# TachSpeedo.net
KiCad netlist of a schematic drawn in EAGLE
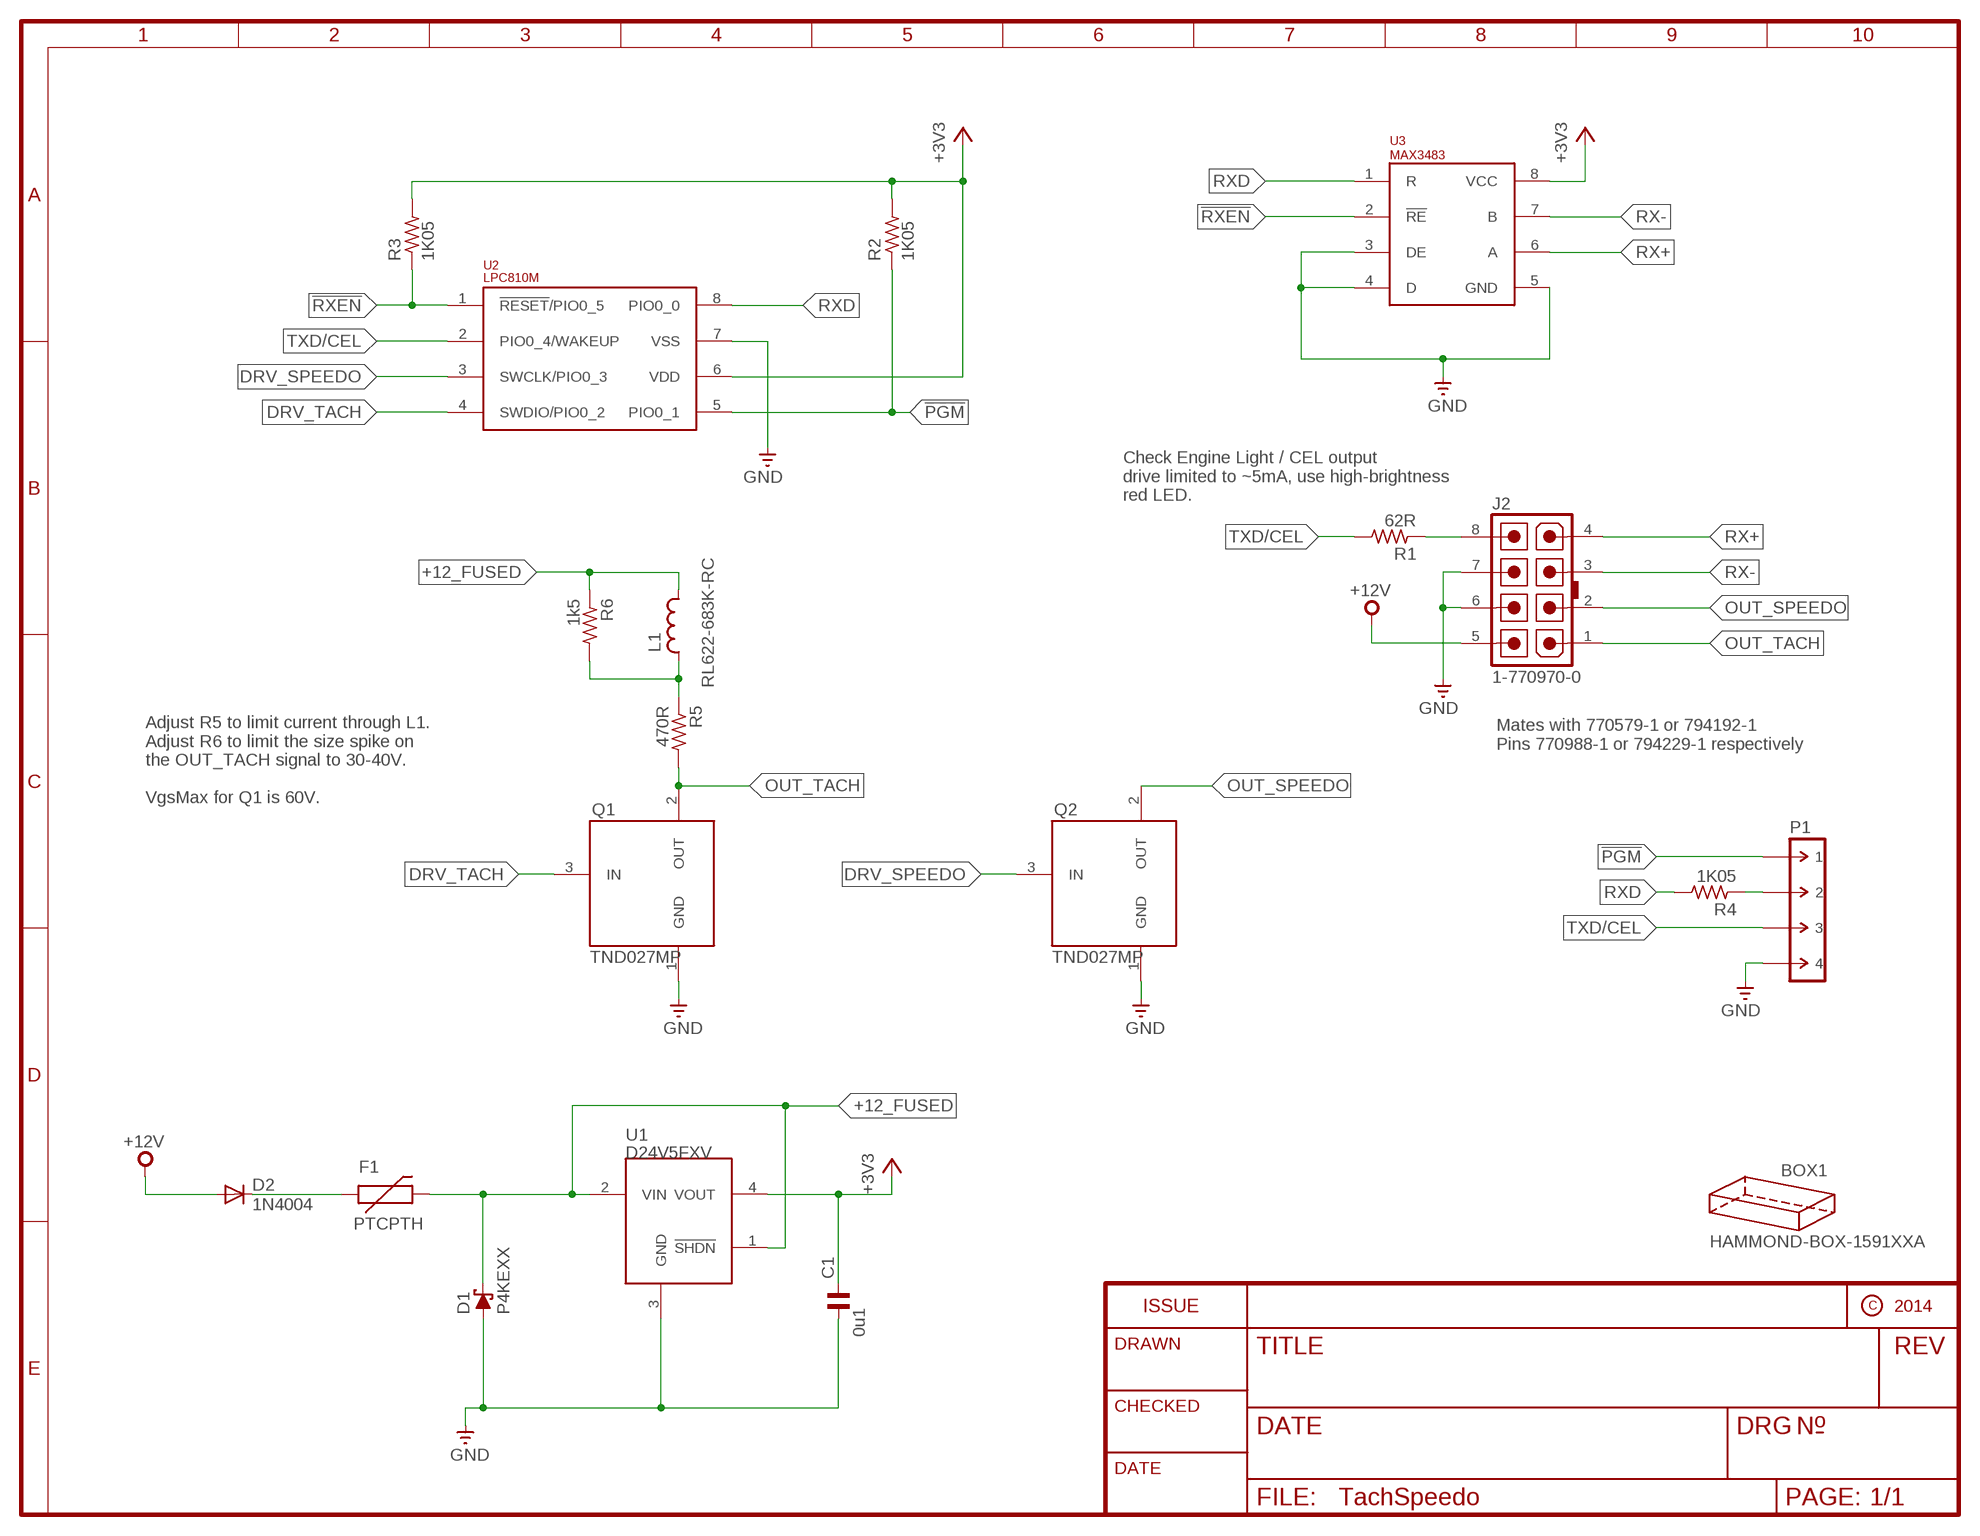
[diagram p0: schematic, sheet 1]

(export (version "E")
  (design (tool "Eeschema 10.0.6"))
  (components
    (comp (ref "BOX1")
      (value "HAMMOND-BOX-1591XXA")
      (footprint "eagle-import:1591XXA")
      (fields (field (name "PARTNO") "1591XXAFLBK"))
      (libsource (lib "eagle-import") (part "HAMMOND-BOX-1591XXA"))
    )
    (comp (ref "C1")
      (value "0u1")
      (footprint "eagle-import:C025-024X044")
      (fields (field (name "PARTNO") "FK18X7R1E104K"))
      (libsource (lib "eagle-import") (part "C-EU025-024X044"))
    )
    (comp (ref "D1")
      (value "P4KEXX")
      (footprint "eagle-import:DO41-10")
      (fields (field (name "PARTNO") "P4KE30CA"))
      (libsource (lib "eagle-import") (part "P4KEXX"))
    )
    (comp (ref "D2")
      (value "1N4004")
      (footprint "eagle-import:DO41-10")
      (libsource (lib "eagle-import") (part "1N4004"))
    )
    (comp (ref "F1")
      (value "PTCPTH")
      (footprint "eagle-import:PTC")
      (fields (field (name "PARTNO") "600R150-RBZR"))
      (libsource (lib "eagle-import") (part "PTCPTH"))
    )
    (comp (ref "J2")
      (value "1-770970-0")
      (footprint "eagle-import:1-770970-0")
      (libsource (lib "eagle-import") (part "1-770970-0"))
    )
    (comp (ref "L1")
      (value "RL622-683K-RC")
      (footprint "eagle-import:RL622")
      (fields (field (name "PARTNO") "RL622-563K-RC"))
      (libsource (lib "eagle-import") (part "RL622"))
    )
    (comp (ref "P1")
      (value "M-1X04-SIP-100-40")
      (footprint "eagle-import:SIP-100-04-40")
      (fields (field (name "PARTNO") "961104-6404-AR"))
      (libsource (lib "eagle-import") (part "M-1X04-SIP-100-40"))
    )
    (comp (ref "Q1")
      (value "TND027MP")
      (footprint "eagle-import:TO-92")
      (fields (field (name "PARTNO") "TND027MP-AZ"))
      (libsource (lib "eagle-import") (part "TND027MP"))
    )
    (comp (ref "Q2")
      (value "TND027MP")
      (footprint "eagle-import:TO-92")
      (fields (field (name "PARTNO") "TND027MP-AZ"))
      (libsource (lib "eagle-import") (part "TND027MP"))
    )
    (comp (ref "R1")
      (value "62R")
      (footprint "eagle-import:0207_10")
      (fields (field (name "PARTNO") "MFR-25FTE52-62R"))
      (libsource (lib "eagle-import") (part "R-EU_0207/10"))
    )
    (comp (ref "R2")
      (value "1K05")
      (footprint "eagle-import:0207_10")
      (fields (field (name "PARTNO") "MFR-25FBF52-1K05"))
      (libsource (lib "eagle-import") (part "R-EU_0207/10"))
    )
    (comp (ref "R3")
      (value "1K05")
      (footprint "eagle-import:0207_10")
      (fields (field (name "PARTNO") "MFR-25FBF52-1K05"))
      (libsource (lib "eagle-import") (part "R-EU_0207/10"))
    )
    (comp (ref "R4")
      (value "1K05")
      (footprint "eagle-import:0207_10")
      (fields (field (name "PARTNO") "MFR-25FBF52-1K05"))
      (libsource (lib "eagle-import") (part "R-EU_0207/10"))
    )
    (comp (ref "R5")
      (value "470R")
      (footprint "eagle-import:0207_10")
      (fields (field (name "PARTNO") "MFR-25FBF52-470R"))
      (libsource (lib "eagle-import") (part "R-EU_0207/10"))
    )
    (comp (ref "R6")
      (value "1k5")
      (footprint "eagle-import:0207_10")
      (fields (field (name "PARTNO") "MFR-25FRF52-1K5"))
      (libsource (lib "eagle-import") (part "R-EU_0207/10"))
    )
    (comp (ref "U1")
      (value "D24V5FXV")
      (footprint "eagle-import:SIP-100-04-40")
      (libsource (lib "eagle-import") (part "D24V5FXV"))
    )
    (comp (ref "U2")
      (value "LPC810M")
      (footprint "eagle-import:DIL08")
      (fields (field (name "PARTNO") "LPC810M021FN8FP"))
      (libsource (lib "eagle-import") (part "LPC810M"))
    )
    (comp (ref "U3")
      (value "MAX3483")
      (footprint "eagle-import:DIL08")
      (fields (field (name "PARTNO") "MAX3483CPA+"))
      (libsource (lib "eagle-import") (part "MAX3483"))
    )
  )
  (nets
    (net (code "1") (name "+3V3") (class "Default")
      (node (ref "C1") (pin "1") (pinfunction "1_1") (pintype "passive"))
      (node (ref "R2") (pin "2") (pinfunction "2_2") (pintype "passive"))
      (node (ref "R3") (pin "2") (pinfunction "2_2") (pintype "passive"))
      (node (ref "U1") (pin "4") (pinfunction "VOUT_4") (pintype "bidirectional"))
      (node (ref "U2") (pin "6") (pinfunction "VDD_6") (pintype "bidirectional"))
      (node (ref "U3") (pin "8") (pinfunction "VCC_8") (pintype "power_in"))
    )
    (net (code "2") (name "+12V") (class "Default")
      (node (ref "D2") (pin "A") (pinfunction "A_A") (pintype "passive"))
      (node (ref "J2") (pin "5") (pinfunction "5_5") (pintype "passive"))
    )
    (net (code "3") (name "+12_FUSED") (class "Default")
      (node (ref "D1") (pin "C") (pinfunction "C_C") (pintype "passive"))
      (node (ref "F1") (pin "P$2") (pinfunction "2_P$2") (pintype "bidirectional"))
      (node (ref "L1") (pin "2") (pinfunction "2_2") (pintype "passive"))
      (node (ref "R6") (pin "1") (pinfunction "1_1") (pintype "passive"))
      (node (ref "U1") (pin "1") (pinfunction "~{SHDN}_1") (pintype "bidirectional"))
      (node (ref "U1") (pin "2") (pinfunction "VIN_2") (pintype "bidirectional"))
    )
    (net (code "4") (name "/~{PGM}") (class "Default")
      (node (ref "P1") (pin "1") (pinfunction "1_1") (pintype "passive"))
      (node (ref "R2") (pin "1") (pinfunction "1_1") (pintype "passive"))
      (node (ref "U2") (pin "5") (pinfunction "PIO0_1_5") (pintype "bidirectional"))
    )
    (net (code "5") (name "/~{RXEN}") (class "Default")
      (node (ref "R3") (pin "1") (pinfunction "1_1") (pintype "passive"))
      (node (ref "U2") (pin "1") (pinfunction "~{RESET}/PIO0_5_1") (pintype "bidirectional"))
      (node (ref "U3") (pin "2") (pinfunction "~{RE}_2") (pintype "input"))
    )
    (net (code "6") (name "DRV_SPEEDO") (class "Default")
      (node (ref "Q2") (pin "3") (pinfunction "IN_3") (pintype "bidirectional"))
      (node (ref "U2") (pin "3") (pinfunction "SWCLK/PIO0_3_3") (pintype "bidirectional"))
    )
    (net (code "7") (name "DRV_TACH") (class "Default")
      (node (ref "Q1") (pin "3") (pinfunction "IN_3") (pintype "bidirectional"))
      (node (ref "U2") (pin "4") (pinfunction "SWDIO/PIO0_2_4") (pintype "bidirectional"))
    )
    (net (code "8") (name "GND") (class "Default")
      (node (ref "C1") (pin "2") (pinfunction "2_2") (pintype "passive"))
      (node (ref "D1") (pin "A") (pinfunction "A_A") (pintype "passive"))
      (node (ref "J2") (pin "6") (pinfunction "6_6") (pintype "passive"))
      (node (ref "J2") (pin "7") (pinfunction "7_7") (pintype "passive"))
      (node (ref "P1") (pin "4") (pinfunction "4_4") (pintype "passive"))
      (node (ref "Q1") (pin "1") (pinfunction "GND_1") (pintype "bidirectional"))
      (node (ref "Q2") (pin "1") (pinfunction "GND_1") (pintype "bidirectional"))
      (node (ref "U1") (pin "3") (pinfunction "GND_3") (pintype "bidirectional"))
      (node (ref "U2") (pin "7") (pinfunction "VSS_7") (pintype "bidirectional"))
      (node (ref "U3") (pin "3") (pinfunction "DE_3") (pintype "input"))
      (node (ref "U3") (pin "4") (pinfunction "D_4") (pintype "input"))
      (node (ref "U3") (pin "5") (pinfunction "GND_5") (pintype "power_in"))
    )
    (net (code "9") (name "Net-(F1-1)") (class "Default")
      (node (ref "D2") (pin "C") (pinfunction "C_C") (pintype "passive"))
      (node (ref "F1") (pin "P$1") (pinfunction "1_P$1") (pintype "bidirectional"))
    )
    (net (code "10") (name "Net-(J2-Pad8)") (class "Default")
      (node (ref "J2") (pin "8") (pinfunction "8_8") (pintype "passive"))
      (node (ref "R1") (pin "1") (pinfunction "1_1") (pintype "passive"))
    )
    (net (code "11") (name "Net-(L1-Pad1)") (class "Default")
      (node (ref "L1") (pin "1") (pinfunction "1_1") (pintype "passive"))
      (node (ref "R5") (pin "1") (pinfunction "1_1") (pintype "passive"))
      (node (ref "R6") (pin "2") (pinfunction "2_2") (pintype "passive"))
    )
    (net (code "12") (name "Net-(P1-Pad2)") (class "Default")
      (node (ref "P1") (pin "2") (pinfunction "2_2") (pintype "passive"))
      (node (ref "R4") (pin "1") (pinfunction "1_1") (pintype "passive"))
    )
    (net (code "13") (name "OUT_SPEEDO") (class "Default")
      (node (ref "J2") (pin "2") (pinfunction "2_2") (pintype "passive"))
      (node (ref "Q2") (pin "2") (pinfunction "OUT_2") (pintype "bidirectional"))
    )
    (net (code "14") (name "OUT_TACH") (class "Default")
      (node (ref "J2") (pin "1") (pinfunction "1_1") (pintype "passive"))
      (node (ref "Q1") (pin "2") (pinfunction "OUT_2") (pintype "bidirectional"))
      (node (ref "R5") (pin "2") (pinfunction "2_2") (pintype "passive"))
    )
    (net (code "15") (name "RX+") (class "Default")
      (node (ref "J2") (pin "4") (pinfunction "4_4") (pintype "passive"))
      (node (ref "U3") (pin "6") (pinfunction "A_6") (pintype "bidirectional"))
    )
    (net (code "16") (name "RX-") (class "Default")
      (node (ref "J2") (pin "3") (pinfunction "3_3") (pintype "passive"))
      (node (ref "U3") (pin "7") (pinfunction "B_7") (pintype "bidirectional"))
    )
    (net (code "17") (name "RXD") (class "Default")
      (node (ref "R4") (pin "2") (pinfunction "2_2") (pintype "passive"))
      (node (ref "U2") (pin "8") (pinfunction "PIO0_0_8") (pintype "bidirectional"))
      (node (ref "U3") (pin "1") (pinfunction "R_1") (pintype "output"))
    )
    (net (code "18") (name "TXD{slash}CEL") (class "Default")
      (node (ref "P1") (pin "3") (pinfunction "3_3") (pintype "passive"))
      (node (ref "R1") (pin "2") (pinfunction "2_2") (pintype "passive"))
      (node (ref "U2") (pin "2") (pinfunction "PIO0_4/WAKEUP_2") (pintype "bidirectional"))
    )
  )
)
